# TaxoOut.net
KiCad netlist of a schematic drawn in Altium Designer
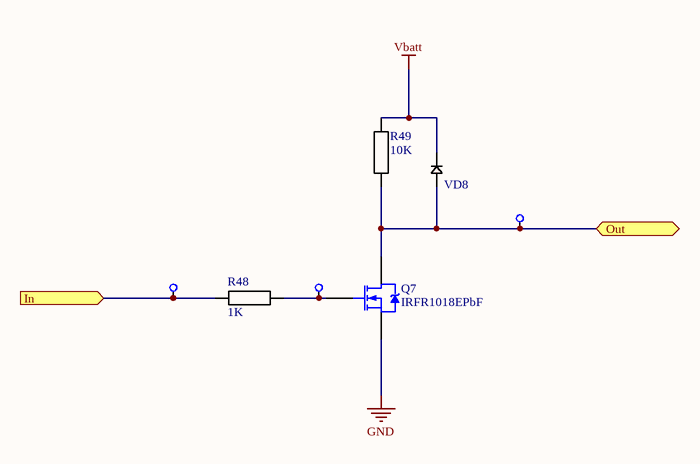
[diagram p0: TaxoOut.SchDoc]

(export (version "E")
  (design (tool "Eeschema 10.0.6"))
  (components
    (comp (ref "Q7")
      (value "IRFR1018EPbF")
      (footprint "DPAK228P991X238-3M")
      (description "HEXFET Power MOSFET")
      (libsource (lib "Maks_lib") (part "IRFR1018EPbF"))
    )
    (comp (ref "R48")
      (value "1K")
      (footprint "SMD 0603")
      (description "RC0603FR-071KL")
      (libsource (lib "Maks_lib") (part "Resistor"))
    )
    (comp (ref "R49")
      (value "10K")
      (footprint "SMD 0603")
      (description "RC0603FR-0710KL")
      (libsource (lib "Maks_lib") (part "Resistor"))
    )
    (comp (ref "TP66")
      (value "TestPoint")
      (footprint "TESTPOINT")
      (description "testPoint")
      (libsource (lib "Maks_lib") (part "TestPoint"))
    )
    (comp (ref "TP67")
      (value "TestPoint")
      (footprint "TESTPOINT")
      (description "testPoint")
      (libsource (lib "Maks_lib") (part "TestPoint"))
    )
    (comp (ref "TP68")
      (value "TestPoint")
      (footprint "TESTPOINT")
      (description "testPoint")
      (libsource (lib "Maks_lib") (part "TestPoint"))
    )
    (comp (ref "VD8")
      (value "Diode")
      (footprint "DO-214AA")
      (description "STTH4R02U 200 V, 4 A High Effiency Ultrafast Diode")
      (libsource (lib "Maks_lib") (part "Diode"))
    )
  )
  (nets
    (net (code "1") (name "/In") (class "Default")
      (node (ref "R48") (pin "2") (pinfunction "2_2") (pintype "passive"))
      (node (ref "TP66") (pin "0") (pinfunction "0_0") (pintype "passive"))
    )
    (net (code "2") (name "/Out") (class "Default")
      (node (ref "Q7") (pin "4") (pinfunction "D_4") (pintype "passive"))
      (node (ref "R49") (pin "1") (pinfunction "1_1") (pintype "passive"))
      (node (ref "TP68") (pin "0") (pinfunction "0_0") (pintype "passive"))
      (node (ref "VD8") (pin "0") (pinfunction "0_0") (pintype "passive"))
    )
    (net (code "3") (name "GND") (class "Default")
      (node (ref "Q7") (pin "3") (pinfunction "S_3") (pintype "passive"))
    )
    (net (code "4") (name "Net-(Q7-G)") (class "Default")
      (node (ref "Q7") (pin "1") (pinfunction "G_1") (pintype "passive"))
      (node (ref "R48") (pin "1") (pinfunction "1_1") (pintype "passive"))
      (node (ref "TP67") (pin "0") (pinfunction "0_0") (pintype "passive"))
    )
    (net (code "5") (name "Vbatt") (class "Default")
      (node (ref "R49") (pin "2") (pinfunction "2_2") (pintype "passive"))
      (node (ref "VD8") (pin "1") (pinfunction "1_1") (pintype "passive"))
    )
  )
)
